# schematics.net
KiCad netlist of a schematic drawn in Altium Designer
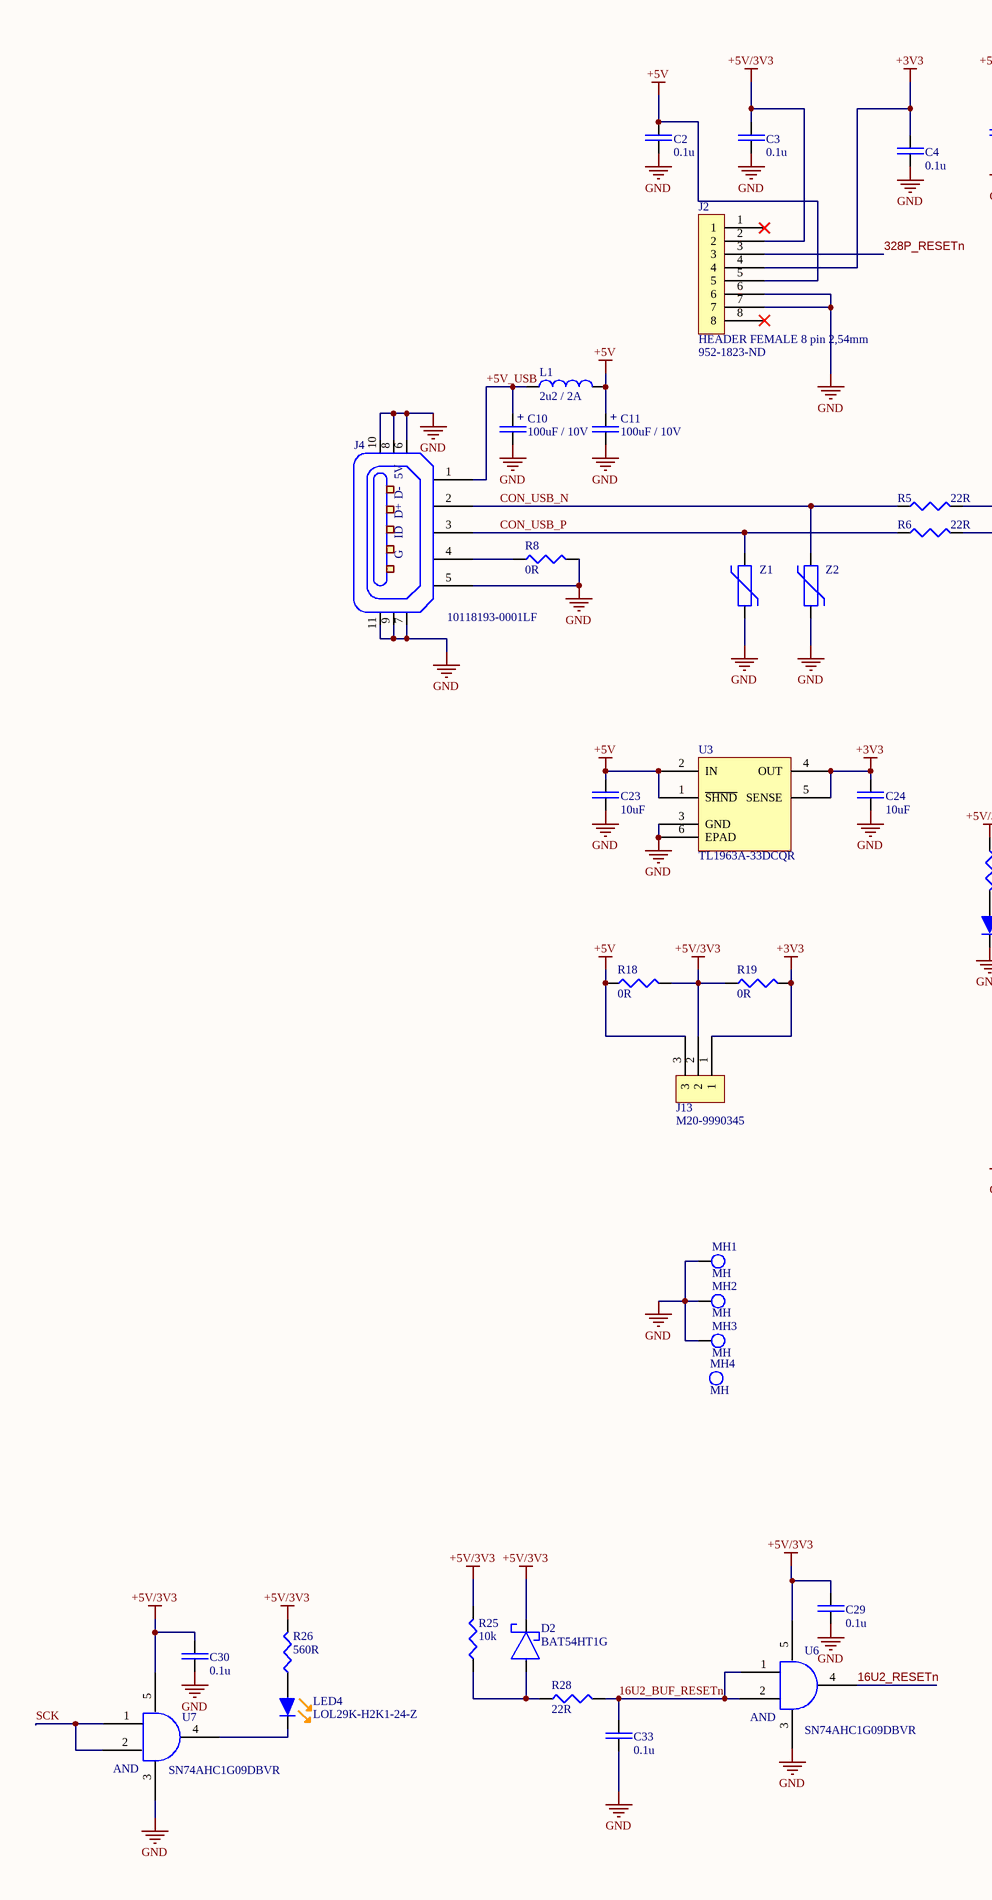
[diagram p0: schematics.SchDoc, left]
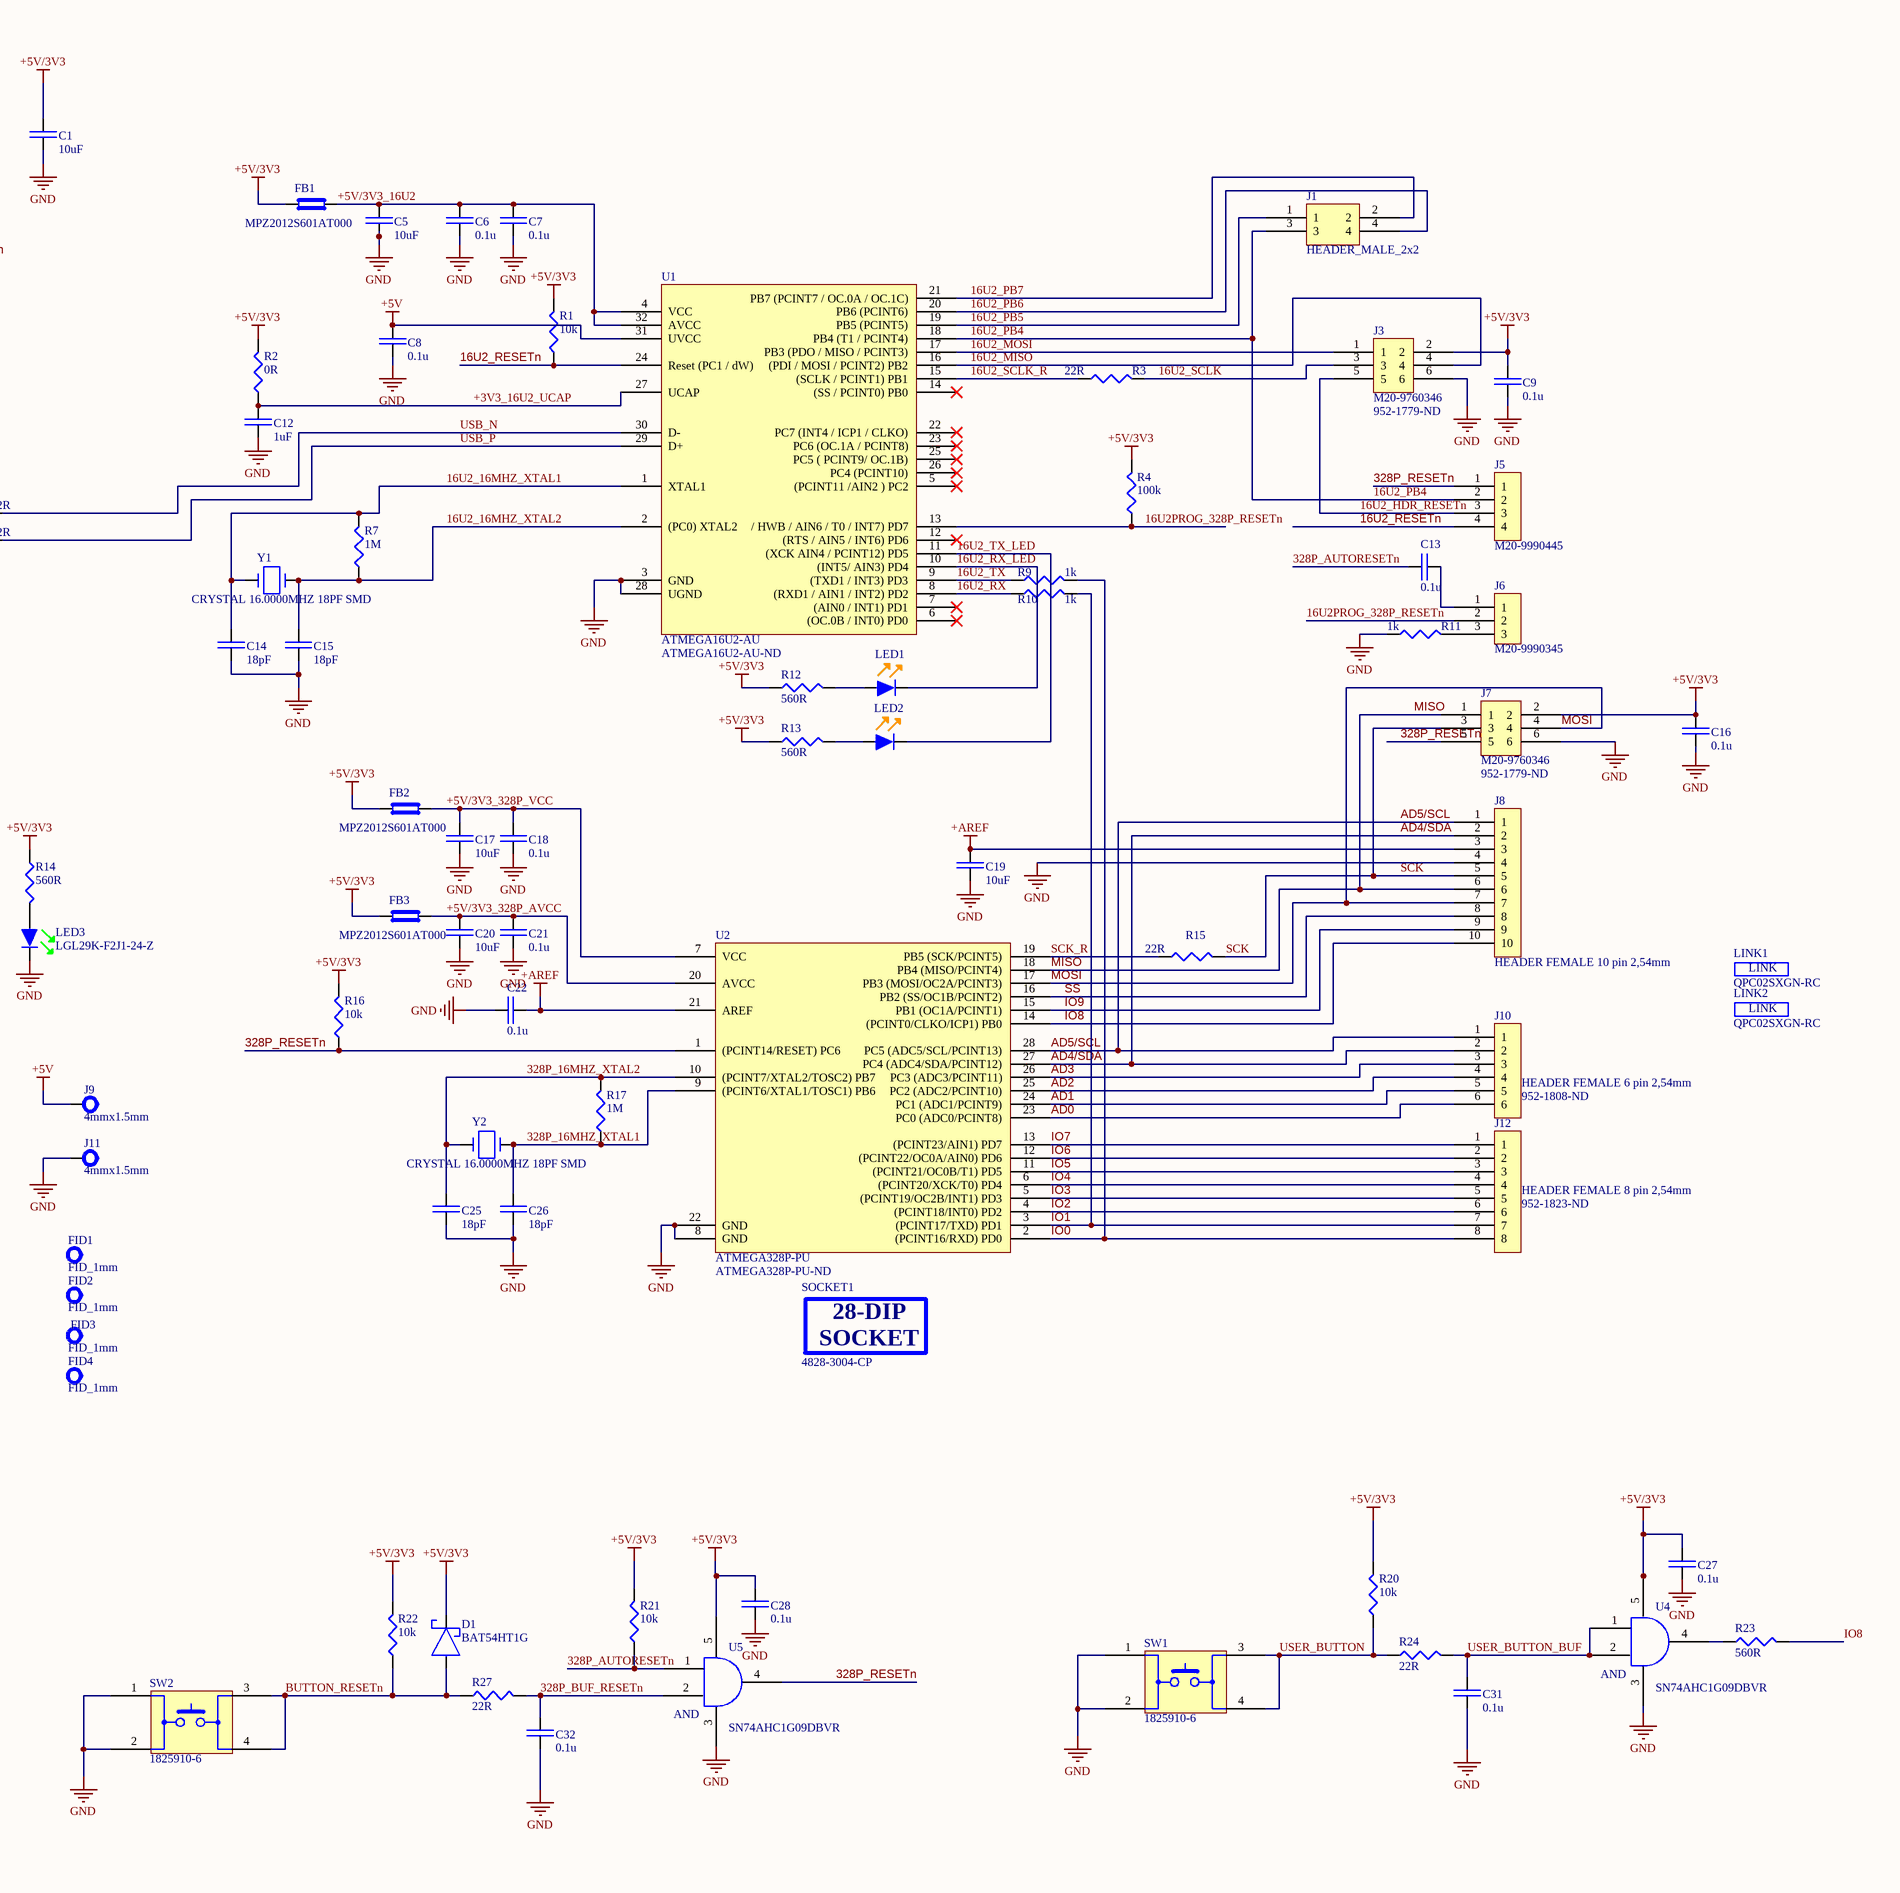
[diagram p1: schematics.SchDoc, right]

(export (version "E")
  (design (tool "Eeschema 10.0.6"))
  (components
    (comp (ref "C1")
      (value "10uF")
      (footprint "CAP_0805")
      (description "Ceramic capacitor SMD 0805 10 µF 16 V 10 %")
      (fields
        (field (name "MANUFACTURER") "Samsung")
        (field (name "MANUFACTURER PART NUMBER") "CL21A106KOQNNNG")
      )
      (libsource (lib "sch_library") (part "CL21A106KOQNNNG"))
    )
    (comp (ref "C2")
      (value "0.1u")
      (footprint "CAP_603")
      (description "CL10 Series 0603 0.1 uF 50 V ±10% Tolerance X7R Multilayer Ceramic Capacitor")
      (fields
        (field (name "MANUFACTURER") "Samsung")
        (field (name "MANUFACTURER PART NUMBER") "CL10B104KB8NNNL")
      )
      (libsource (lib "sch_library") (part "CL10B104KB8NNNL"))
    )
    (comp (ref "C3")
      (value "0.1u")
      (footprint "CAP_603")
      (description "CL10 Series 0603 0.1 uF 50 V ±10% Tolerance X7R Multilayer Ceramic Capacitor")
      (fields
        (field (name "MANUFACTURER") "Samsung")
        (field (name "MANUFACTURER PART NUMBER") "CL10B104KB8NNNL")
      )
      (libsource (lib "sch_library") (part "CL10B104KB8NNNL"))
    )
    (comp (ref "C4")
      (value "0.1u")
      (footprint "CAP_603")
      (description "CL10 Series 0603 0.1 uF 50 V ±10% Tolerance X7R Multilayer Ceramic Capacitor")
      (fields
        (field (name "MANUFACTURER") "Samsung")
        (field (name "MANUFACTURER PART NUMBER") "CL10B104KB8NNNL")
      )
      (libsource (lib "sch_library") (part "CL10B104KB8NNNL"))
    )
    (comp (ref "C5")
      (value "10uF")
      (footprint "CAP_0805")
      (description "Ceramic capacitor SMD 0805 10 µF 16 V 10 %")
      (fields
        (field (name "MANUFACTURER") "Samsung")
        (field (name "MANUFACTURER PART NUMBER") "CL21A106KOQNNNG")
      )
      (libsource (lib "sch_library") (part "CL21A106KOQNNNG"))
    )
    (comp (ref "C6")
      (value "0.1u")
      (footprint "CAP_603")
      (description "CL10 Series 0603 0.1 uF 50 V ±10% Tolerance X7R Multilayer Ceramic Capacitor")
      (fields
        (field (name "MANUFACTURER") "Samsung")
        (field (name "MANUFACTURER PART NUMBER") "CL10B104KB8NNNL")
      )
      (libsource (lib "sch_library") (part "CL10B104KB8NNNL"))
    )
    (comp (ref "C7")
      (value "0.1u")
      (footprint "CAP_603")
      (description "CL10 Series 0603 0.1 uF 50 V ±10% Tolerance X7R Multilayer Ceramic Capacitor")
      (fields
        (field (name "MANUFACTURER") "Samsung")
        (field (name "MANUFACTURER PART NUMBER") "CL10B104KB8NNNL")
      )
      (libsource (lib "sch_library") (part "CL10B104KB8NNNL"))
    )
    (comp (ref "C8")
      (value "0.1u")
      (footprint "CAP_603")
      (description "CL10 Series 0603 0.1 uF 50 V ±10% Tolerance X7R Multilayer Ceramic Capacitor")
      (fields
        (field (name "MANUFACTURER") "Samsung")
        (field (name "MANUFACTURER PART NUMBER") "CL10B104KB8NNNL")
      )
      (libsource (lib "sch_library") (part "CL10B104KB8NNNL"))
    )
    (comp (ref "C9")
      (value "0.1u")
      (footprint "CAP_603")
      (description "CL10 Series 0603 0.1 uF 50 V ±10% Tolerance X7R Multilayer Ceramic Capacitor")
      (fields
        (field (name "MANUFACTURER") "Samsung")
        (field (name "MANUFACTURER PART NUMBER") "CL10B104KB8NNNL")
      )
      (libsource (lib "sch_library") (part "CL10B104KB8NNNL"))
    )
    (comp (ref "C10")
      (value "100uF / 10V")
      (footprint "EEE-1AA101WR")
      (description "Cap Aluminum 100uF 10V 20% (5 X 5.4mm) SMD 50mA 1000 hr 85°C T/R")
      (fields
        (field (name "MANUFACTURER") "Panasonic")
        (field (name "MANUFACTURER PART NUMBER") "EEE-1AA101WR")
      )
      (libsource (lib "sch_library") (part "EEE-1AA101WR"))
    )
    (comp (ref "C11")
      (value "100uF / 10V")
      (footprint "EEE-1AA101WR")
      (description "Cap Aluminum 100uF 10V 20% (5 X 5.4mm) SMD 50mA 1000 hr 85°C T/R")
      (fields
        (field (name "MANUFACTURER") "Panasonic")
        (field (name "MANUFACTURER PART NUMBER") "EEE-1AA101WR")
      )
      (libsource (lib "sch_library") (part "EEE-1AA101WR"))
    )
    (comp (ref "C12")
      (value "1uF")
      (footprint "CAP_603")
      (fields
        (field (name "MANUFACTURER") "Yageo")
        (field (name "MANUFACTURER PART NUMBER") "CC0603KRX5R8BB105")
        (field (name "TOLERANCE") "10%")
      )
      (libsource (lib "sch_library") (part "CC0603KRX5R8BB105"))
    )
    (comp (ref "C13")
      (value "0.1u")
      (footprint "CAP_603")
      (description "CL10 Series 0603 0.1 uF 50 V ±10% Tolerance X7R Multilayer Ceramic Capacitor")
      (fields
        (field (name "MANUFACTURER") "Samsung")
        (field (name "MANUFACTURER PART NUMBER") "CL10B104KB8NNNL")
      )
      (libsource (lib "sch_library") (part "CL10B104KB8NNNL"))
    )
    (comp (ref "C14")
      (value "18pF")
      (footprint "CAP_603")
      (description "0603 18 pF 50V ±5% Tolerance C0G/NP0 Surface Mount Multilayer Ceramic Capacitor")
      (fields
        (field (name "MANUFACTURER") "Kyocera AVX")
        (field (name "MANUFACTURER PART NUMBER") "06035A180JAT2A")
      )
      (libsource (lib "sch_library") (part "06035A180JAT2A"))
    )
    (comp (ref "C15")
      (value "18pF")
      (footprint "CAP_603")
      (description "0603 18 pF 50V ±5% Tolerance C0G/NP0 Surface Mount Multilayer Ceramic Capacitor")
      (fields
        (field (name "MANUFACTURER") "Kyocera AVX")
        (field (name "MANUFACTURER PART NUMBER") "06035A180JAT2A")
      )
      (libsource (lib "sch_library") (part "06035A180JAT2A"))
    )
    (comp (ref "C16")
      (value "0.1u")
      (footprint "CAP_603")
      (description "CL10 Series 0603 0.1 uF 50 V ±10% Tolerance X7R Multilayer Ceramic Capacitor")
      (fields
        (field (name "MANUFACTURER") "Samsung")
        (field (name "MANUFACTURER PART NUMBER") "CL10B104KB8NNNL")
      )
      (libsource (lib "sch_library") (part "CL10B104KB8NNNL"))
    )
    (comp (ref "C17")
      (value "10uF")
      (footprint "CAP_0805")
      (description "Ceramic capacitor SMD 0805 10 µF 16 V 10 %")
      (fields
        (field (name "MANUFACTURER") "Samsung")
        (field (name "MANUFACTURER PART NUMBER") "CL21A106KOQNNNG")
      )
      (libsource (lib "sch_library") (part "CL21A106KOQNNNG"))
    )
    (comp (ref "C18")
      (value "0.1u")
      (footprint "CAP_603")
      (description "CL10 Series 0603 0.1 uF 50 V ±10% Tolerance X7R Multilayer Ceramic Capacitor")
      (fields
        (field (name "MANUFACTURER") "Samsung")
        (field (name "MANUFACTURER PART NUMBER") "CL10B104KB8NNNL")
      )
      (libsource (lib "sch_library") (part "CL10B104KB8NNNL"))
    )
    (comp (ref "C19")
      (value "10uF")
      (footprint "CAP_0805")
      (description "Ceramic capacitor SMD 0805 10 µF 16 V 10 %")
      (fields
        (field (name "MANUFACTURER") "Samsung")
        (field (name "MANUFACTURER PART NUMBER") "CL21A106KOQNNNG")
      )
      (libsource (lib "sch_library") (part "CL21A106KOQNNNG"))
    )
    (comp (ref "C20")
      (value "10uF")
      (footprint "CAP_0805")
      (description "Ceramic capacitor SMD 0805 10 µF 16 V 10 %")
      (fields
        (field (name "MANUFACTURER") "Samsung")
        (field (name "MANUFACTURER PART NUMBER") "CL21A106KOQNNNG")
      )
      (libsource (lib "sch_library") (part "CL21A106KOQNNNG"))
    )
    (comp (ref "C21")
      (value "0.1u")
      (footprint "CAP_603")
      (description "CL10 Series 0603 0.1 uF 50 V ±10% Tolerance X7R Multilayer Ceramic Capacitor")
      (fields
        (field (name "MANUFACTURER") "Samsung")
        (field (name "MANUFACTURER PART NUMBER") "CL10B104KB8NNNL")
      )
      (libsource (lib "sch_library") (part "CL10B104KB8NNNL"))
    )
    (comp (ref "C22")
      (value "0.1u")
      (footprint "CAP_603")
      (description "CL10 Series 0603 0.1 uF 50 V ±10% Tolerance X7R Multilayer Ceramic Capacitor")
      (fields
        (field (name "MANUFACTURER") "Samsung")
        (field (name "MANUFACTURER PART NUMBER") "CL10B104KB8NNNL")
      )
      (libsource (lib "sch_library") (part "CL10B104KB8NNNL"))
    )
    (comp (ref "C23")
      (value "10uF")
      (footprint "CAP_0805")
      (description "Ceramic capacitor SMD 0805 10 µF 16 V 10 %")
      (fields
        (field (name "MANUFACTURER") "Samsung")
        (field (name "MANUFACTURER PART NUMBER") "CL21A106KOQNNNG")
      )
      (libsource (lib "sch_library") (part "CL21A106KOQNNNG"))
    )
    (comp (ref "C24")
      (value "10uF")
      (footprint "CAP_0805")
      (description "Ceramic capacitor SMD 0805 10 µF 16 V 10 %")
      (fields
        (field (name "MANUFACTURER") "Samsung")
        (field (name "MANUFACTURER PART NUMBER") "CL21A106KOQNNNG")
      )
      (libsource (lib "sch_library") (part "CL21A106KOQNNNG"))
    )
    (comp (ref "C25")
      (value "18pF")
      (footprint "CAP_603")
      (description "0603 18 pF 50V ±5% Tolerance C0G/NP0 Surface Mount Multilayer Ceramic Capacitor")
      (fields
        (field (name "MANUFACTURER") "Kyocera AVX")
        (field (name "MANUFACTURER PART NUMBER") "06035A180JAT2A")
      )
      (libsource (lib "sch_library") (part "06035A180JAT2A"))
    )
    (comp (ref "C26")
      (value "18pF")
      (footprint "CAP_603")
      (description "0603 18 pF 50V ±5% Tolerance C0G/NP0 Surface Mount Multilayer Ceramic Capacitor")
      (fields
        (field (name "MANUFACTURER") "Kyocera AVX")
        (field (name "MANUFACTURER PART NUMBER") "06035A180JAT2A")
      )
      (libsource (lib "sch_library") (part "06035A180JAT2A"))
    )
    (comp (ref "C27")
      (value "0.1u")
      (footprint "CAP_603")
      (description "CL10 Series 0603 0.1 uF 50 V ±10% Tolerance X7R Multilayer Ceramic Capacitor")
      (fields
        (field (name "MANUFACTURER") "Samsung")
        (field (name "MANUFACTURER PART NUMBER") "CL10B104KB8NNNL")
      )
      (libsource (lib "sch_library") (part "CL10B104KB8NNNL"))
    )
    (comp (ref "C28")
      (value "0.1u")
      (footprint "CAP_603")
      (description "CL10 Series 0603 0.1 uF 50 V ±10% Tolerance X7R Multilayer Ceramic Capacitor")
      (fields
        (field (name "MANUFACTURER") "Samsung")
        (field (name "MANUFACTURER PART NUMBER") "CL10B104KB8NNNL")
      )
      (libsource (lib "sch_library") (part "CL10B104KB8NNNL"))
    )
    (comp (ref "C29")
      (value "0.1u")
      (footprint "CAP_603")
      (description "CL10 Series 0603 0.1 uF 50 V ±10% Tolerance X7R Multilayer Ceramic Capacitor")
      (fields
        (field (name "MANUFACTURER") "Samsung")
        (field (name "MANUFACTURER PART NUMBER") "CL10B104KB8NNNL")
      )
      (libsource (lib "sch_library") (part "CL10B104KB8NNNL"))
    )
    (comp (ref "C30")
      (value "0.1u")
      (footprint "CAP_603")
      (description "CL10 Series 0603 0.1 uF 50 V ±10% Tolerance X7R Multilayer Ceramic Capacitor")
      (fields
        (field (name "MANUFACTURER") "Samsung")
        (field (name "MANUFACTURER PART NUMBER") "CL10B104KB8NNNL")
      )
      (libsource (lib "sch_library") (part "CL10B104KB8NNNL"))
    )
    (comp (ref "C31")
      (value "0.1u")
      (footprint "CAP_603")
      (description "CL10 Series 0603 0.1 uF 50 V ±10% Tolerance X7R Multilayer Ceramic Capacitor")
      (fields
        (field (name "MANUFACTURER") "Samsung")
        (field (name "MANUFACTURER PART NUMBER") "CL10B104KB8NNNL")
      )
      (libsource (lib "sch_library") (part "CL10B104KB8NNNL"))
    )
    (comp (ref "C32")
      (value "0.1u")
      (footprint "CAP_603")
      (description "CL10 Series 0603 0.1 uF 50 V ±10% Tolerance X7R Multilayer Ceramic Capacitor")
      (fields
        (field (name "MANUFACTURER") "Samsung")
        (field (name "MANUFACTURER PART NUMBER") "CL10B104KB8NNNL")
      )
      (libsource (lib "sch_library") (part "CL10B104KB8NNNL"))
    )
    (comp (ref "C33")
      (value "0.1u")
      (footprint "CAP_603")
      (description "CL10 Series 0603 0.1 uF 50 V ±10% Tolerance X7R Multilayer Ceramic Capacitor")
      (fields
        (field (name "MANUFACTURER") "Samsung")
        (field (name "MANUFACTURER PART NUMBER") "CL10B104KB8NNNL")
      )
      (libsource (lib "sch_library") (part "CL10B104KB8NNNL"))
    )
    (comp (ref "D1")
      (value "BAT54HT1G")
      (footprint "BAT54HT1G")
      (description "Small Signal Schottky Diode, Single, 30 V, 200 mA, 800 mV, 600 mA, 150 C ;RoHS Compliant: Yes")
      (fields (field (name "MANUFACTURER") "ON Semiconductor / Fairchild"))
      (libsource (lib "sch_library") (part "BAT54HT1G"))
    )
    (comp (ref "D2")
      (value "BAT54HT1G")
      (footprint "BAT54HT1G")
      (description "Small Signal Schottky Diode, Single, 30 V, 200 mA, 800 mV, 600 mA, 150 C ;RoHS Compliant: Yes")
      (fields (field (name "MANUFACTURER") "ON Semiconductor / Fairchild"))
      (libsource (lib "sch_library") (part "BAT54HT1G"))
    )
    (comp (ref "FB1")
      (value "MPZ2012S601AT000")
      (footprint "FB_0805")
      (description "FERRITE BEAD 600 OHM 0805 1LN")
      (fields (field (name "MANUFACTURER") "TDK"))
      (libsource (lib "sch_library") (part "MPZ2012S601AT000"))
    )
    (comp (ref "FB2")
      (value "MPZ2012S601AT000")
      (footprint "FB_0805")
      (description "FERRITE BEAD 600 OHM 0805 1LN")
      (fields (field (name "MANUFACTURER") "TDK"))
      (libsource (lib "sch_library") (part "MPZ2012S601AT000"))
    )
    (comp (ref "FB3")
      (value "MPZ2012S601AT000")
      (footprint "FB_0805")
      (description "FERRITE BEAD 600 OHM 0805 1LN")
      (fields (field (name "MANUFACTURER") "TDK"))
      (libsource (lib "sch_library") (part "MPZ2012S601AT000"))
    )
    (comp (ref "FID1")
      (value "FID_1mm")
      (footprint "FID_1mm")
      (description "Fiducial 1mm")
      (libsource (lib "sch_library") (part "FID_1mm"))
    )
    (comp (ref "FID2")
      (value "FID_1mm")
      (footprint "FID_1mm")
      (description "Fiducial 1mm")
      (libsource (lib "sch_library") (part "FID_1mm"))
    )
    (comp (ref "FID3")
      (value "FID_1mm")
      (footprint "FID_1mm")
      (description "Fiducial 1mm")
      (libsource (lib "sch_library") (part "FID_1mm"))
    )
    (comp (ref "FID4")
      (value "FID_1mm")
      (footprint "FID_1mm")
      (description "Fiducial 1mm")
      (libsource (lib "sch_library") (part "FID_1mm"))
    )
    (comp (ref "J1")
      (value "HEADER_MALE_2x2")
      (footprint "HEADER_MALE_2x2PIN")
      (description "02+02 DIL Vert Pin Hdr")
      (fields (field (name "MANUFACTURER") "Harwin") (field (name "MANUFACTURER PART NUMBER") "M20-9760246"))
      (libsource (lib "sch_library") (part "M20-9760246"))
    )
    (comp (ref "J2")
      (value "HEADER FEMALE 8 pin 2,54mm")
      (footprint "HEADER_FEMALE_8PIN_2.54mm")
      (description "2.54mm (0.1\") Pitch SIL Vertical PC Tail Socket Assembly, selective gold + tin, 8 contacts")
      (fields
        (field (name "MANUFACTURER") "Harwin")
        (field (name "MANUFACTURER PART NUMBER") "M20-7820842")
        (field (name "SUPPLIER PART NUMBER 1") "952-1823-ND")
      )
      (libsource (lib "sch_library") (part "M20-7820842"))
    )
    (comp (ref "J3")
      (value "M20-9760346")
      (footprint "HEADER_MALE_2x3PIN")
      (description "03+03 DIL VERT PIN HDR")
      (fields (field (name "MANUFACTURER") "Harwin") (field (name "SUPPLIER PART NUMBER 1") "952-1779-ND"))
      (libsource (lib "sch_library") (part "M20-9760346"))
    )
    (comp (ref "J4")
      (value "10118193-0001LF")
      (footprint "10118193-0001LF")
      (description "CONN USB MICRO B RECPT SMT R/A")
      (fields (field (name "MANUFACTURER") "Amphenol FCI"))
      (libsource (lib "sch_library") (part "10118193-0001LF"))
    )
    (comp (ref "J5")
      (value "M20-9990445")
      (footprint "HEADER_MALE_1x4")
      (fields (field (name "MANUFACTURER") "Harwin"))
      (libsource (lib "sch_library") (part "M20-9990445"))
    )
    (comp (ref "J6")
      (value "M20-9990345")
      (footprint "HEADER_MALE_1x3")
      (fields (field (name "MANUFACTURER") "Harwin"))
      (libsource (lib "sch_library") (part "M20-9990345"))
    )
    (comp (ref "J7")
      (value "M20-9760346")
      (footprint "HEADER_MALE_2x3PIN")
      (description "03+03 DIL VERT PIN HDR")
      (fields (field (name "MANUFACTURER") "Harwin") (field (name "SUPPLIER PART NUMBER 1") "952-1779-ND"))
      (libsource (lib "sch_library") (part "M20-9760346"))
    )
    (comp (ref "J8")
      (value "HEADER FEMALE 10 pin 2,54mm")
      (footprint "HEADER_FEMALE_10PIN_2.54mm")
      (description "Headers & Wire Housings 10 PIN SIL VERTICAL SOCKET GOLD+TIN")
      (fields (field (name "MANUFACTURER") "Harwin") (field (name "MANUFACTURER PART NUMBER") "M20-7821042"))
      (libsource (lib "sch_library") (part "M20-7821042"))
    )
    (comp (ref "J9")
      (value "4mmx1.5mm")
      (footprint "PAD_WITH_HOLE_4mmx1.5mm")
      (libsource (lib "sch_library") (part "PAD_WITH_HOLE_4mmx1.5mm"))
    )
    (comp (ref "J10")
      (value "HEADER FEMALE 6 pin 2,54mm")
      (footprint "HEADER_FEMALE_6PIN_2.54mm")
      (description "Conn Socket Strip SKT 6 POS 2.54mm Solder ST Thru-Hole Tube")
      (fields
        (field (name "MANUFACTURER") "Harwin")
        (field (name "MANUFACTURER PART NUMBER") "M20-7820642")
        (field (name "SUPPLIER PART NUMBER 1") "952-1808-ND")
      )
      (libsource (lib "sch_library") (part "M20-7820642"))
    )
    (comp (ref "J11")
      (value "4mmx1.5mm")
      (footprint "PAD_WITH_HOLE_4mmx1.5mm")
      (libsource (lib "sch_library") (part "PAD_WITH_HOLE_4mmx1.5mm"))
    )
    (comp (ref "J12")
      (value "HEADER FEMALE 8 pin 2,54mm")
      (footprint "HEADER_FEMALE_8PIN_2.54mm")
      (description "2.54mm (0.1\") Pitch SIL Vertical PC Tail Socket Assembly, selective gold + tin, 8 contacts")
      (fields
        (field (name "MANUFACTURER") "Harwin")
        (field (name "MANUFACTURER PART NUMBER") "M20-7820842")
        (field (name "SUPPLIER PART NUMBER 1") "952-1823-ND")
      )
      (libsource (lib "") (part "M20-7820842_1"))
    )
    (comp (ref "J13")
      (value "M20-9990345")
      (footprint "HEADER_MALE_1x3")
      (fields (field (name "MANUFACTURER") "Harwin"))
      (libsource (lib "") (part "M20-9990345_1"))
    )
    (comp (ref "L1")
      (value "2u2 / 2A")
      (footprint "L_1210")
      (description "FIXED IND 2.2UH 2A 80 MOHM SMD")
      (fields
        (field (name "MANUFACTURER") "KEMET")
        (field (name "MANUFACTURER PART NUMBER") "L1210R2R2MDWIT")
      )
      (libsource (lib "sch_library") (part "L1210R2R2MDWIT"))
    )
    (comp (ref "LED1")
      (value "LOL29K-H2K1-24-Z")
      (footprint "LED_0603")
      (description "OSRAM - LO L29K-H2K1-24-Z - SMARTLED 0603 ORANGE")
      (fields (field (name "MANUFACTURER") "Osram Opto"))
      (libsource (lib "sch_library") (part "LOL29K-H2K1-24-Z"))
    )
    (comp (ref "LED2")
      (value "LOL29K-H2K1-24-Z")
      (footprint "LED_0603")
      (description "OSRAM - LO L29K-H2K1-24-Z - SMARTLED 0603 ORANGE")
      (fields (field (name "MANUFACTURER") "Osram Opto"))
      (libsource (lib "sch_library") (part "LOL29K-H2K1-24-Z"))
    )
    (comp (ref "LED3")
      (value "LGL29K-F2J1-24-Z")
      (footprint "LED_0603")
      (description "LED Uni-Color Green 572nm Automotive 2-Pin Chip 0603(1608Metric) T/R")
      (fields (field (name "MANUFACTURER") "Osram Opto"))
      (libsource (lib "sch_library") (part "LGL29K-F2J1-24-Z"))
    )
    (comp (ref "LED4")
      (value "LOL29K-H2K1-24-Z")
      (footprint "LED_0603")
      (description "OSRAM - LO L29K-H2K1-24-Z - SMARTLED 0603 ORANGE")
      (fields (field (name "MANUFACTURER") "Osram Opto"))
      (libsource (lib "sch_library") (part "LOL29K-H2K1-24-Z"))
    )
    (comp (ref "LINK1")
      (value "QPC02SXGN-RC")
      (description "CONN JUMPER SHORTING .100\" GOLD")
      (fields (field (name "MANUFACTURER") "Sullins"))
      (libsource (lib "sch_library") (part "QPC02SXGN-RC"))
    )
    (comp (ref "LINK2")
      (value "QPC02SXGN-RC")
      (description "CONN JUMPER SHORTING .100\" GOLD")
      (fields (field (name "MANUFACTURER") "Sullins"))
      (libsource (lib "sch_library") (part "QPC02SXGN-RC"))
    )
    (comp (ref "MH1")
      (value "MH")
      (footprint "MH_7.4mm_3,2MMD")
      (description "MH_7.4mm_3,2MMD")
      (libsource (lib "sch_library") (part "MH_7.4mm_3,2MMD"))
    )
    (comp (ref "MH2")
      (value "MH")
      (footprint "MH_7.4mm_3,2MMD")
      (description "MH_7.4mm_3,2MMD")
      (libsource (lib "sch_library") (part "MH_7.4mm_3,2MMD"))
    )
    (comp (ref "MH3")
      (value "MH")
      (footprint "MH_7.4mm_3,2MMD")
      (description "MH_7.4mm_3,2MMD")
      (libsource (lib "sch_library") (part "MH_7.4mm_3,2MMD"))
    )
    (comp (ref "MH4")
      (value "MH")
      (footprint "MH_7.4mm_3,2MMD_nonplated")
      (description "MH_7.4mm_3,2MMD non plated")
      (libsource (lib "sch_library") (part "MH_7.4mm_3,2MMD_non_plated"))
    )
    (comp (ref "R1")
      (value "10k")
      (footprint "R_0603")
      (description "RES SMD 10K OHM 1% 1/10W 0603")
      (fields
        (field (name "MANUFACTURER") "Yageo")
        (field (name "MANUFACTURER PART NUMBER") "AC0603FR-0710KL")
      )
      (libsource (lib "sch_library") (part "AC0603FR-0710KL"))
    )
    (comp (ref "R2")
      (value "0R")
      (footprint "R_0603")
      (description "YAGEO - RC0603FR-070RL - RES, THICK FILM, 0R, 1%, 0.1W, 0603")
      (fields
        (field (name "MANUFACTURER") "Yageo")
        (field (name "MANUFACTURER PART NUMBER") "RC0603FR-070RL")
      )
      (libsource (lib "sch_library") (part "RC0603FR-070RL"))
    )
    (comp (ref "R3")
      (value "22R")
      (footprint "R_0805")
      (description "RES SMD 22 OHM 1% 1/8W 0805")
      (fields
        (field (name "MANUFACTURER") "Yageo")
        (field (name "MANUFACTURER PART NUMBER") "RC0805FR-0722RL")
      )
      (libsource (lib "sch_library") (part "RC0805FR-0722RL"))
    )
    (comp (ref "R4")
      (value "100k")
      (footprint "R_0603")
      (description "Res Thick Film 1.6 x 0.8 mm 100K Ohm 1% 0.1W(1/10W) 100ppm/ C Molded SMD Paper T/R")
      (fields
        (field (name "MANUFACTURER") "Yageo")
        (field (name "MANUFACTURER PART NUMBER") "RC0603FR-07100KL")
      )
      (libsource (lib "sch_library") (part "RC0603FR-07100KL"))
    )
    (comp (ref "R5")
      (value "22R")
      (footprint "R_0805")
      (description "RES SMD 22 OHM 1% 1/8W 0805")
      (fields
        (field (name "MANUFACTURER") "Yageo")
        (field (name "MANUFACTURER PART NUMBER") "RC0805FR-0722RL")
      )
      (libsource (lib "sch_library") (part "RC0805FR-0722RL"))
    )
    (comp (ref "R6")
      (value "22R")
      (footprint "R_0805")
      (description "RES SMD 22 OHM 1% 1/8W 0805")
      (fields
        (field (name "MANUFACTURER") "Yageo")
        (field (name "MANUFACTURER PART NUMBER") "RC0805FR-0722RL")
      )
      (libsource (lib "sch_library") (part "RC0805FR-0722RL"))
    )
    (comp (ref "R7")
      (value "1M")
      (footprint "R_0603")
      (description "Yageo RC Series Thick Film Surface Mount Resistor 0603 Case 1M 1% 0.1W 100ppm/C")
      (fields
        (field (name "MANUFACTURER") "Yageo")
        (field (name "MANUFACTURER PART NUMBER") "RC0603FR-071ML")
      )
      (libsource (lib "sch_library") (part "RC0603FR-071ML"))
    )
    (comp (ref "R8")
      (value "0R")
      (footprint "R_0603")
      (description "YAGEO - RC0603FR-070RL - RES, THICK FILM, 0R, 1%, 0.1W, 0603")
      (fields
        (field (name "MANUFACTURER") "Yageo")
        (field (name "MANUFACTURER PART NUMBER") "RC0603FR-070RL")
      )
      (libsource (lib "sch_library") (part "RC0603FR-070RL"))
    )
    (comp (ref "R9")
      (value "1k")
      (footprint "R_0603")
      (description "Res Thick Film 0603 1K Ohm 1% 0.1W(1/10W) ±100ppm/C Epoxy Pad SMD Automotive T/R")
      (fields
        (field (name "MANUFACTURER") "Yageo")
        (field (name "MANUFACTURER PART NUMBER") "AC0603FR-071KL")
      )
      (libsource (lib "sch_library") (part "AC0603FR-071KL"))
    )
    (comp (ref "R10")
      (value "1k")
      (footprint "R_0603")
      (description "Res Thick Film 0603 1K Ohm 1% 0.1W(1/10W) ±100ppm/C Epoxy Pad SMD Automotive T/R")
      (fields
        (field (name "MANUFACTURER") "Yageo")
        (field (name "MANUFACTURER PART NUMBER") "AC0603FR-071KL")
      )
      (libsource (lib "sch_library") (part "AC0603FR-071KL"))
    )
    (comp (ref "R11")
      (value "1k")
      (footprint "R_0603")
      (description "Res Thick Film 0603 1K Ohm 1% 0.1W(1/10W) ±100ppm/C Epoxy Pad SMD Automotive T/R")
      (fields
        (field (name "MANUFACTURER") "Yageo")
        (field (name "MANUFACTURER PART NUMBER") "AC0603FR-071KL")
      )
      (libsource (lib "sch_library") (part "AC0603FR-071KL"))
    )
    (comp (ref "R12")
      (value "560R")
      (footprint "R_0603")
      (fields
        (field (name "MANUFACTURER") "Yageo")
        (field (name "MANUFACTURER PART NUMBER") "RC0603FR-07560RL")
        (field (name "TOLERANCE") "1%")
      )
      (libsource (lib "sch_library") (part "560R"))
    )
    (comp (ref "R13")
      (value "560R")
      (footprint "R_0603")
      (fields
        (field (name "MANUFACTURER") "Yageo")
        (field (name "MANUFACTURER PART NUMBER") "RC0603FR-07560RL")
        (field (name "TOLERANCE") "1%")
      )
      (libsource (lib "sch_library") (part "560R"))
    )
    (comp (ref "R14")
      (value "560R")
      (footprint "R_0603")
      (fields
        (field (name "MANUFACTURER") "Yageo")
        (field (name "MANUFACTURER PART NUMBER") "RC0603FR-07560RL")
        (field (name "TOLERANCE") "1%")
      )
      (libsource (lib "sch_library") (part "560R"))
    )
    (comp (ref "R15")
      (value "22R")
      (footprint "R_0805")
      (description "RES SMD 22 OHM 1% 1/8W 0805")
      (fields
        (field (name "MANUFACTURER") "Yageo")
        (field (name "MANUFACTURER PART NUMBER") "RC0805FR-0722RL")
      )
      (libsource (lib "sch_library") (part "RC0805FR-0722RL"))
    )
    (comp (ref "R16")
      (value "10k")
      (footprint "R_0603")
      (description "RES SMD 10K OHM 1% 1/10W 0603")
      (fields
        (field (name "MANUFACTURER") "Yageo")
        (field (name "MANUFACTURER PART NUMBER") "AC0603FR-0710KL")
      )
      (libsource (lib "sch_library") (part "AC0603FR-0710KL"))
    )
    (comp (ref "R17")
      (value "1M")
      (footprint "R_0603")
      (description "Yageo RC Series Thick Film Surface Mount Resistor 0603 Case 1M 1% 0.1W 100ppm/C")
      (fields
        (field (name "MANUFACTURER") "Yageo")
        (field (name "MANUFACTURER PART NUMBER") "RC0603FR-071ML")
      )
      (libsource (lib "sch_library") (part "RC0603FR-071ML"))
    )
    (comp (ref "R18")
      (value "0R")
      (footprint "R_0603")
      (description "YAGEO - RC0603FR-070RL - RES, THICK FILM, 0R, 1%, 0.1W, 0603")
      (fields
        (field (name "MANUFACTURER") "Yageo")
        (field (name "MANUFACTURER PART NUMBER") "RC0603FR-070RL")
      )
      (libsource (lib "sch_library") (part "RC0603FR-070RL"))
    )
    (comp (ref "R19")
      (value "0R")
      (footprint "R_0603")
      (description "YAGEO - RC0603FR-070RL - RES, THICK FILM, 0R, 1%, 0.1W, 0603")
      (fields
        (field (name "MANUFACTURER") "Yageo")
        (field (name "MANUFACTURER PART NUMBER") "RC0603FR-070RL")
      )
      (libsource (lib "sch_library") (part "RC0603FR-070RL"))
    )
    (comp (ref "R20")
      (value "10k")
      (footprint "R_0603")
      (description "RES SMD 10K OHM 1% 1/10W 0603")
      (fields
        (field (name "MANUFACTURER") "Yageo")
        (field (name "MANUFACTURER PART NUMBER") "AC0603FR-0710KL")
      )
      (libsource (lib "sch_library") (part "AC0603FR-0710KL"))
    )
    (comp (ref "R21")
      (value "10k")
      (footprint "R_0603")
      (description "RES SMD 10K OHM 1% 1/10W 0603")
      (fields
        (field (name "MANUFACTURER") "Yageo")
        (field (name "MANUFACTURER PART NUMBER") "AC0603FR-0710KL")
      )
      (libsource (lib "sch_library") (part "AC0603FR-0710KL"))
    )
    (comp (ref "R22")
      (value "10k")
      (footprint "R_0603")
      (description "RES SMD 10K OHM 1% 1/10W 0603")
      (fields
        (field (name "MANUFACTURER") "Yageo")
        (field (name "MANUFACTURER PART NUMBER") "AC0603FR-0710KL")
      )
      (libsource (lib "sch_library") (part "AC0603FR-0710KL"))
    )
    (comp (ref "R23")
      (value "560R")
      (footprint "R_0603")
      (fields
        (field (name "MANUFACTURER") "Yageo")
        (field (name "MANUFACTURER PART NUMBER") "RC0603FR-07560RL")
        (field (name "TOLERANCE") "1%")
      )
      (libsource (lib "sch_library") (part "560R"))
    )
    (comp (ref "R24")
      (value "22R")
      (footprint "R_0805")
      (description "RES SMD 22 OHM 1% 1/8W 0805")
      (fields
        (field (name "MANUFACTURER") "Yageo")
        (field (name "MANUFACTURER PART NUMBER") "RC0805FR-0722RL")
      )
      (libsource (lib "sch_library") (part "RC0805FR-0722RL"))
    )
    (comp (ref "R25")
      (value "10k")
      (footprint "R_0603")
      (description "RES SMD 10K OHM 1% 1/10W 0603")
      (fields
        (field (name "MANUFACTURER") "Yageo")
        (field (name "MANUFACTURER PART NUMBER") "AC0603FR-0710KL")
      )
      (libsource (lib "sch_library") (part "AC0603FR-0710KL"))
    )
    (comp (ref "R26")
      (value "560R")
      (footprint "R_0603")
      (fields
        (field (name "MANUFACTURER") "Yageo")
        (field (name "MANUFACTURER PART NUMBER") "RC0603FR-07560RL")
        (field (name "TOLERANCE") "1%")
      )
      (libsource (lib "sch_library") (part "560R"))
    )
    (comp (ref "R27")
      (value "22R")
      (footprint "R_0805")
      (description "RES SMD 22 OHM 1% 1/8W 0805")
      (fields
        (field (name "MANUFACTURER") "Yageo")
        (field (name "MANUFACTURER PART NUMBER") "RC0805FR-0722RL")
      )
      (libsource (lib "sch_library") (part "RC0805FR-0722RL"))
    )
    (comp (ref "R28")
      (value "22R")
      (footprint "R_0805")
      (description "RES SMD 22 OHM 1% 1/8W 0805")
      (fields
        (field (name "MANUFACTURER") "Yageo")
        (field (name "MANUFACTURER PART NUMBER") "RC0805FR-0722RL")
      )
      (libsource (lib "sch_library") (part "RC0805FR-0722RL"))
    )
    (comp (ref "SOCKET1")
      (value "4828-3004-CP")
      (description "CONN IC DIP SOCKET 28POS TIN")
      (fields (field (name "MANUFACTURER") "3M"))
      (libsource (lib "sch_library") (part "4828-3004-CP"))
    )
    (comp (ref "SW1")
      (value "1825910-6")
      (footprint "BUTTON")
      (description "SWITCH TACTILE SPST-NO 0.05A 24V")
      (fields (field (name "MANUFACTURER") "TE Connectivity Alcoswitch"))
      (libsource (lib "sch_library") (part "1825910-6"))
    )
    (comp (ref "SW2")
      (value "1825910-6")
      (footprint "BUTTON")
      (description "SWITCH TACTILE SPST-NO 0.05A 24V")
      (fields (field (name "MANUFACTURER") "TE Connectivity Alcoswitch"))
      (libsource (lib "sch_library") (part "1825910-6"))
    )
    (comp (ref "U1")
      (value "ATMEGA16U2-AU")
      (footprint "TQFP32")
      (description "MICROCHIP - ATMEGA16U2-AU - MCU, 8BIT, MEGAAVR, 16MHZ, TQFP-32")
      (fields
        (field (name "MANUFACTURER") "Microchip / Atmel")
        (field (name "SUPPLIER PART NUMBER 1") "ATMEGA16U2-AU-ND")
      )
      (libsource (lib "sch_library") (part "ATMEGA16U2-AU"))
    )
    (comp (ref "U2")
      (value "ATMEGA328P-PU")
      (footprint "DIP28_7.62mm")
      (description "ATMEGA328P-PU; 8 bit Microcontroller AVR 20MHz 1; 32kb Flash; 2kb RAM; I2C SPI 2")
      (fields
        (field (name "MANUFACTURER") "Microchip / Atmel")
        (field (name "SUPPLIER PART NUMBER 1") "ATMEGA328P-PU-ND")
      )
      (libsource (lib "sch_library") (part "ATMEGA328P-PU"))
    )
    (comp (ref "U3")
      (value "TL1963A-33DCQR")
      (footprint "DCQ (R-PDSO-G6)")
      (description "IC REG LINEAR 3.3V 1.5A SOT223-6")
      (fields (field (name "MANUFACTURER") "Texas Instruments"))
      (libsource (lib "sch_library") (part "TL1963A-33DCQR"))
    )
    (comp (ref "U4")
      (value "SN74AHC1G09DBVR")
      (footprint "SOT-23")
      (description "TEXAS INSTRUMENTS - SN74AHC1G09DBVR - AND Gate, 74AHC1G09, 2 Input, 2 V to 5.5 V, SOT-23-5")
      (fields (field (name "MANUFACTURER") "Texas Instruments"))
      (libsource (lib "sch_library") (part "SN74AHC1G09DBVR"))
    )
    (comp (ref "U5")
      (value "SN74AHC1G09DBVR")
      (footprint "SOT-23")
      (description "TEXAS INSTRUMENTS - SN74AHC1G09DBVR - AND Gate, 74AHC1G09, 2 Input, 2 V to 5.5 V, SOT-23-5")
      (fields (field (name "MANUFACTURER") "Texas Instruments"))
      (libsource (lib "sch_library") (part "SN74AHC1G09DBVR"))
    )
    (comp (ref "U6")
      (value "SN74AHC1G09DBVR")
      (footprint "SOT-23")
      (description "TEXAS INSTRUMENTS - SN74AHC1G09DBVR - AND Gate, 74AHC1G09, 2 Input, 2 V to 5.5 V, SOT-23-5")
      (fields (field (name "MANUFACTURER") "Texas Instruments"))
      (libsource (lib "sch_library") (part "SN74AHC1G09DBVR"))
    )
    (comp (ref "U7")
      (value "SN74AHC1G09DBVR")
      (footprint "SOT-23")
      (description "TEXAS INSTRUMENTS - SN74AHC1G09DBVR - AND Gate, 74AHC1G09, 2 Input, 2 V to 5.5 V, SOT-23-5")
      (fields (field (name "MANUFACTURER") "Texas Instruments"))
      (libsource (lib "sch_library") (part "SN74AHC1G09DBVR"))
    )
    (comp (ref "Y1")
      (value "CRYSTAL 16.0000MHZ 18PF SMD")
      (footprint "ABM7_v1_1_BIG")
      (fields
        (field (name "MANUFACTURER") "Abracon")
        (field (name "MANUFACTURER PART NUMBER") "ABM7-16.000MHZ-D2Y-T")
        (field (name "TOLERANCE") "20ppm")
      )
      (libsource (lib "sch_library") (part "ABM7-16.000MHZ-D2Y-T"))
    )
    (comp (ref "Y2")
      (value "CRYSTAL 16.0000MHZ 18PF SMD")
      (footprint "ABM7_v1_1_BIG")
      (fields
        (field (name "MANUFACTURER") "Abracon")
        (field (name "MANUFACTURER PART NUMBER") "ABM7-16.000MHZ-D2Y-T")
        (field (name "TOLERANCE") "20ppm")
      )
      (libsource (lib "sch_library") (part "ABM7-16.000MHZ-D2Y-T"))
    )
    (comp (ref "Z1")
      (value "CG0603MLC-05E")
      (footprint "CG0603MLC-05E")
      (description "VARISTOR 0603")
      (fields (field (name "MANUFACTURER") "Bourns") (field (name "VOLTAGE") "5V"))
      (libsource (lib "sch_library") (part "CG0603MLC-05E"))
    )
    (comp (ref "Z2")
      (value "CG0603MLC-05E")
      (footprint "CG0603MLC-05E")
      (description "VARISTOR 0603")
      (fields (field (name "MANUFACTURER") "Bourns") (field (name "VOLTAGE") "5V"))
      (libsource (lib "sch_library") (part "CG0603MLC-05E"))
    )
  )
  (nets
    (net (code "1") (name "+3V3") (class "Default")
      (node (ref "C24") (pin "2") (pinfunction "2_2") (pintype "passive"))
      (node (ref "C4") (pin "1") (pinfunction "1_1") (pintype "passive"))
      (node (ref "J13") (pin "1") (pinfunction "1_1") (pintype "passive"))
      (node (ref "J2") (pin "4") (pinfunction "4_4") (pintype "passive"))
      (node (ref "R19") (pin "2") (pinfunction "2_2") (pintype "passive"))
      (node (ref "U3") (pin "4") (pinfunction "OUT_4") (pintype "passive"))
      (node (ref "U3") (pin "5") (pinfunction "SENSE_5") (pintype "passive"))
    )
    (net (code "2") (name "+5V") (class "Default")
      (node (ref "C11") (pin "1") (pinfunction "1_1") (pintype "passive"))
      (node (ref "C2") (pin "1") (pinfunction "1_1") (pintype "passive"))
      (node (ref "C23") (pin "2") (pinfunction "2_2") (pintype "passive"))
      (node (ref "C8") (pin "2") (pinfunction "2_2") (pintype "passive"))
      (node (ref "J13") (pin "3") (pinfunction "3_3") (pintype "passive"))
      (node (ref "J2") (pin "5") (pinfunction "5_5") (pintype "passive"))
      (node (ref "J9") (pin "1") (pinfunction "1_1") (pintype "passive"))
      (node (ref "L1") (pin "2") (pinfunction "2_2") (pintype "passive"))
      (node (ref "R18") (pin "1") (pinfunction "1_1") (pintype "passive"))
      (node (ref "U1") (pin "31") (pinfunction "UVCC_31") (pintype "passive"))
      (node (ref "U3") (pin "1") (pinfunction "~{SHND}_1") (pintype "passive"))
      (node (ref "U3") (pin "2") (pinfunction "IN_2") (pintype "passive"))
    )
    (net (code "3") (name "+5V{slash}3V3") (class "Default")
      (node (ref "C1") (pin "2") (pinfunction "2_2") (pintype "passive"))
      (node (ref "C16") (pin "2") (pinfunction "2_2") (pintype "passive"))
      (node (ref "C27") (pin "1") (pinfunction "1_1") (pintype "passive"))
      (node (ref "C28") (pin "1") (pinfunction "1_1") (pintype "passive"))
      (node (ref "C29") (pin "1") (pinfunction "1_1") (pintype "passive"))
      (node (ref "C3") (pin "1") (pinfunction "1_1") (pintype "passive"))
      (node (ref "C30") (pin "2") (pinfunction "2_2") (pintype "passive"))
      (node (ref "C9") (pin "2") (pinfunction "2_2") (pintype "passive"))
      (node (ref "D1") (pin "1") (pinfunction "1_1") (pintype "passive"))
      (node (ref "D2") (pin "1") (pinfunction "1_1") (pintype "passive"))
      (node (ref "FB1") (pin "1") (pinfunction "1_1") (pintype "passive"))
      (node (ref "FB2") (pin "1") (pinfunction "1_1") (pintype "passive"))
      (node (ref "FB3") (pin "1") (pinfunction "1_1") (pintype "passive"))
      (node (ref "J13") (pin "2") (pinfunction "2_2") (pintype "passive"))
      (node (ref "J2") (pin "2") (pinfunction "2_2") (pintype "passive"))
      (node (ref "J3") (pin "2") (pinfunction "2_2") (pintype "passive"))
      (node (ref "J7") (pin "2") (pinfunction "2_2") (pintype "passive"))
      (node (ref "R1") (pin "2") (pinfunction "2_2") (pintype "passive"))
      (node (ref "R12") (pin "1") (pinfunction "1_1") (pintype "passive"))
      (node (ref "R13") (pin "1") (pinfunction "1_1") (pintype "passive"))
      (node (ref "R14") (pin "1") (pinfunction "1_1") (pintype "passive"))
      (node (ref "R16") (pin "2") (pinfunction "2_2") (pintype "passive"))
      (node (ref "R18") (pin "2") (pinfunction "2_2") (pintype "passive"))
      (node (ref "R19") (pin "1") (pinfunction "1_1") (pintype "passive"))
      (node (ref "R2") (pin "2") (pinfunction "2_2") (pintype "passive"))
      (node (ref "R20") (pin "2") (pinfunction "2_2") (pintype "passive"))
      (node (ref "R21") (pin "2") (pinfunction "2_2") (pintype "passive"))
      (node (ref "R22") (pin "2") (pinfunction "2_2") (pintype "passive"))
      (node (ref "R25") (pin "2") (pinfunction "2_2") (pintype "passive"))
      (node (ref "R26") (pin "2") (pinfunction "2_2") (pintype "passive"))
      (node (ref "R4") (pin "2") (pinfunction "2_2") (pintype "passive"))
      (node (ref "U4") (pin "5") (pinfunction "5_5") (pintype "passive"))
      (node (ref "U5") (pin "5") (pinfunction "5_5") (pintype "passive"))
      (node (ref "U6") (pin "5") (pinfunction "5_5") (pintype "passive"))
      (node (ref "U7") (pin "5") (pinfunction "5_5") (pintype "passive"))
    )
    (net (code "4") (name "+AREF") (class "Default")
      (node (ref "C19") (pin "2") (pinfunction "2_2") (pintype "passive"))
      (node (ref "C22") (pin "2") (pinfunction "2_2") (pintype "passive"))
      (node (ref "J8") (pin "3") (pinfunction "3_3") (pintype "passive"))
      (node (ref "U2") (pin "21") (pinfunction "AREF_21") (pintype "passive"))
    )
    (net (code "5") (name "/+3V3_16U2_UCAP") (class "Default")
      (node (ref "C12") (pin "2") (pinfunction "2_2") (pintype "passive"))
      (node (ref "R2") (pin "1") (pinfunction "1_1") (pintype "passive"))
      (node (ref "U1") (pin "27") (pinfunction "UCAP_27") (pintype "passive"))
    )
    (net (code "6") (name "/+5V_USB") (class "Default")
      (node (ref "C10") (pin "1") (pinfunction "1_1") (pintype "passive"))
      (node (ref "J4") (pin "1") (pinfunction "1_1") (pintype "passive"))
      (node (ref "L1") (pin "1") (pinfunction "1_1") (pintype "passive"))
    )
    (net (code "7") (name "/+5V{slash}3V3_16U2") (class "Default")
      (node (ref "C5") (pin "2") (pinfunction "2_2") (pintype "passive"))
      (node (ref "C6") (pin "2") (pinfunction "2_2") (pintype "passive"))
      (node (ref "C7") (pin "2") (pinfunction "2_2") (pintype "passive"))
      (node (ref "FB1") (pin "2") (pinfunction "2_2") (pintype "passive"))
      (node (ref "U1") (pin "32") (pinfunction "AVCC_32") (pintype "passive"))
      (node (ref "U1") (pin "4") (pinfunction "VCC_4") (pintype "passive"))
    )
    (net (code "8") (name "/+5V{slash}3V3_328P_AVCC") (class "Default")
      (node (ref "C20") (pin "2") (pinfunction "2_2") (pintype "passive"))
      (node (ref "C21") (pin "2") (pinfunction "2_2") (pintype "passive"))
      (node (ref "FB3") (pin "2") (pinfunction "2_2") (pintype "passive"))
      (node (ref "U2") (pin "20") (pinfunction "AVCC_20") (pintype "passive"))
    )
    (net (code "9") (name "/+5V{slash}3V3_328P_VCC") (class "Default")
      (node (ref "C17") (pin "2") (pinfunction "2_2") (pintype "passive"))
      (node (ref "C18") (pin "2") (pinfunction "2_2") (pintype "passive"))
      (node (ref "FB2") (pin "2") (pinfunction "2_2") (pintype "passive"))
      (node (ref "U2") (pin "7") (pinfunction "VCC_7") (pintype "passive"))
    )
    (net (code "10") (name "/16U2PROG_328P_RESETn") (class "Default")
      (node (ref "J6") (pin "2") (pinfunction "2_2") (pintype "passive"))
      (node (ref "R4") (pin "1") (pinfunction "1_1") (pintype "passive"))
      (node (ref "U1") (pin "13") (pinfunction "/_HWB_/_AIN6_/_T0_/_INT7)_PD7_13") (pintype "passive"))
    )
    (net (code "11") (name "/16U2_16MHZ_XTAL1") (class "Default")
      (node (ref "C14") (pin "2") (pinfunction "2_2") (pintype "passive"))
      (node (ref "R7") (pin "2") (pinfunction "2_2") (pintype "passive"))
      (node (ref "U1") (pin "1") (pinfunction "XTAL1_1") (pintype "passive"))
      (node (ref "Y1") (pin "1") (pinfunction "1_1") (pintype "passive"))
    )
    (net (code "12") (name "/16U2_16MHZ_XTAL2") (class "Default")
      (node (ref "C15") (pin "2") (pinfunction "2_2") (pintype "passive"))
      (node (ref "R7") (pin "1") (pinfunction "1_1") (pintype "passive"))
      (node (ref "U1") (pin "2") (pinfunction "(PC0)_XTAL2_2") (pintype "passive"))
      (node (ref "Y1") (pin "2") (pinfunction "2_2") (pintype "passive"))
    )
    (net (code "13") (name "/16U2_BUF_RESETn") (class "Default")
      (node (ref "C33") (pin "2") (pinfunction "2_2") (pintype "passive"))
      (node (ref "R28") (pin "2") (pinfunction "2_2") (pintype "passive"))
      (node (ref "U6") (pin "1") (pinfunction "1_1") (pintype "passive"))
      (node (ref "U6") (pin "2") (pinfunction "2_2") (pintype "passive"))
    )
    (net (code "14") (name "/16U2_HDR_RESETn") (class "Default")
      (node (ref "J3") (pin "5") (pinfunction "5_5") (pintype "passive"))
      (node (ref "J5") (pin "3") (pinfunction "3_3") (pintype "passive"))
    )
    (net (code "15") (name "/16U2_MISO") (class "Default")
      (node (ref "J3") (pin "4") (pinfunction "4_4") (pintype "passive"))
      (node (ref "U1") (pin "16") (pinfunction "(PDI_/_MOSI_/_PCINT2)_PB2_16") (pintype "passive"))
    )
    (net (code "16") (name "/16U2_MOSI") (class "Default")
      (node (ref "J3") (pin "1") (pinfunction "1_1") (pintype "passive"))
      (node (ref "U1") (pin "17") (pinfunction "PB3_(PDO_/_MISO_/_PCINT3)_17") (pintype "passive"))
    )
    (net (code "17") (name "/16U2_PB4") (class "Default")
      (node (ref "J1") (pin "3") (pinfunction "3_3") (pintype "passive"))
      (node (ref "J5") (pin "2") (pinfunction "2_2") (pintype "passive"))
      (node (ref "U1") (pin "18") (pinfunction "PB4_(T1_/_PCINT4)_18") (pintype "passive"))
    )
    (net (code "18") (name "/16U2_PB5") (class "Default")
      (node (ref "J1") (pin "1") (pinfunction "1_1") (pintype "passive"))
      (node (ref "U1") (pin "19") (pinfunction "PB5_(PCINT5)_19") (pintype "passive"))
    )
    (net (code "19") (name "/16U2_PB6") (class "Default")
      (node (ref "J1") (pin "4") (pinfunction "4_4") (pintype "passive"))
      (node (ref "U1") (pin "20") (pinfunction "PB6_(PCINT6)_20") (pintype "passive"))
    )
    (net (code "20") (name "/16U2_PB7") (class "Default")
      (node (ref "J1") (pin "2") (pinfunction "2_2") (pintype "passive"))
      (node (ref "U1") (pin "21") (pinfunction "PB7_(PCINT7_/_OC.0A_/_OC.1C)_21") (pintype "passive"))
    )
    (net (code "21") (name "/16U2_RESETn") (class "Default")
      (node (ref "J5") (pin "4") (pinfunction "4_4") (pintype "passive"))
      (node (ref "R1") (pin "1") (pinfunction "1_1") (pintype "passive"))
      (node (ref "U1") (pin "24") (pinfunction "Reset_(PC1_/_dW)_24") (pintype "passive"))
      (node (ref "U6") (pin "4") (pinfunction "4_4") (pintype "passive"))
    )
    (net (code "22") (name "/16U2_RX") (class "Default")
      (node (ref "R10") (pin "1") (pinfunction "1_1") (pintype "passive"))
      (node (ref "U1") (pin "8") (pinfunction "(RXD1_/_AIN1_/_INT2)_PD2_8") (pintype "passive"))
    )
    (net (code "23") (name "/16U2_RX_LED") (class "Default")
      (node (ref "LED1") (pin "1") (pinfunction "1_1") (pintype "passive"))
      (node (ref "U1") (pin "10") (pinfunction "(INT5/_AIN3)_PD4_10") (pintype "passive"))
    )
    (net (code "24") (name "/16U2_SCLK") (class "Default")
      (node (ref "J3") (pin "3") (pinfunction "3_3") (pintype "passive"))
      (node (ref "R3") (pin "2") (pinfunction "2_2") (pintype "passive"))
    )
    (net (code "25") (name "/16U2_SCLK_R") (class "Default")
      (node (ref "R3") (pin "1") (pinfunction "1_1") (pintype "passive"))
      (node (ref "U1") (pin "15") (pinfunction "(SCLK_/_PCINT1)_PB1_15") (pintype "passive"))
    )
    (net (code "26") (name "/16U2_TX") (class "Default")
      (node (ref "R9") (pin "1") (pinfunction "1_1") (pintype "passive"))
      (node (ref "U1") (pin "9") (pinfunction "(TXD1_/_INT3)_PD3_9") (pintype "passive"))
    )
    (net (code "27") (name "/16U2_TX_LED") (class "Default")
      (node (ref "LED2") (pin "1") (pinfunction "1_1") (pintype "passive"))
      (node (ref "U1") (pin "11") (pinfunction "(XCK_AIN4_/_PCINT12)_PD5_11") (pintype "passive"))
    )
    (net (code "28") (name "/328P_16MHZ_XTAL1") (class "Default")
      (node (ref "C26") (pin "2") (pinfunction "2_2") (pintype "passive"))
      (node (ref "R17") (pin "1") (pinfunction "1_1") (pintype "passive"))
      (node (ref "U2") (pin "9") (pinfunction "(PCINT6/XTAL1/TOSC1)_PB6_9") (pintype "passive"))
      (node (ref "Y2") (pin "2") (pinfunction "2_2") (pintype "passive"))
    )
    (net (code "29") (name "/328P_16MHZ_XTAL2") (class "Default")
      (node (ref "C25") (pin "2") (pinfunction "2_2") (pintype "passive"))
      (node (ref "R17") (pin "2") (pinfunction "2_2") (pintype "passive"))
      (node (ref "U2") (pin "10") (pinfunction "(PCINT7/XTAL2/TOSC2)_PB7_10") (pintype "passive"))
      (node (ref "Y2") (pin "1") (pinfunction "1_1") (pintype "passive"))
    )
    (net (code "30") (name "/328P_AUTORESETn") (class "Default")
      (node (ref "C13") (pin "1") (pinfunction "1_1") (pintype "passive"))
      (node (ref "R21") (pin "1") (pinfunction "1_1") (pintype "passive"))
      (node (ref "U5") (pin "1") (pinfunction "1_1") (pintype "passive"))
    )
    (net (code "31") (name "/328P_BUF_RESETn") (class "Default")
      (node (ref "C32") (pin "2") (pinfunction "2_2") (pintype "passive"))
      (node (ref "R27") (pin "2") (pinfunction "2_2") (pintype "passive"))
      (node (ref "U5") (pin "2") (pinfunction "2_2") (pintype "passive"))
    )
    (net (code "32") (name "/328P_RESETn") (class "Default")
      (node (ref "J2") (pin "3") (pinfunction "3_3") (pintype "passive"))
      (node (ref "J5") (pin "1") (pinfunction "1_1") (pintype "passive"))
      (node (ref "J7") (pin "5") (pinfunction "5_5") (pintype "passive"))
      (node (ref "R16") (pin "1") (pinfunction "1_1") (pintype "passive"))
      (node (ref "U2") (pin "1") (pinfunction "(PCINT14/RESET)_PC6_1") (pintype "passive"))
      (node (ref "U5") (pin "4") (pinfunction "4_4") (pintype "passive"))
    )
    (net (code "33") (name "/AD0") (class "Default")
      (node (ref "J10") (pin "6") (pinfunction "6_6") (pintype "passive"))
      (node (ref "U2") (pin "23") (pinfunction "PC0_(ADC0/PCINT8)_23") (pintype "passive"))
    )
    (net (code "34") (name "/AD1") (class "Default")
      (node (ref "J10") (pin "5") (pinfunction "5_5") (pintype "passive"))
      (node (ref "U2") (pin "24") (pinfunction "PC1_(ADC1/PCINT9)_24") (pintype "passive"))
    )
    (net (code "35") (name "/AD2") (class "Default")
      (node (ref "J10") (pin "4") (pinfunction "4_4") (pintype "passive"))
      (node (ref "U2") (pin "25") (pinfunction "PC2_(ADC2/PCINT10)_25") (pintype "passive"))
    )
    (net (code "36") (name "/AD3") (class "Default")
      (node (ref "J10") (pin "3") (pinfunction "3_3") (pintype "passive"))
      (node (ref "U2") (pin "26") (pinfunction "PC3_(ADC3/PCINT11)_26") (pintype "passive"))
    )
    (net (code "37") (name "/AD4{slash}SDA") (class "Default")
      (node (ref "J10") (pin "2") (pinfunction "2_2") (pintype "passive"))
      (node (ref "J8") (pin "2") (pinfunction "2_2") (pintype "passive"))
      (node (ref "U2") (pin "27") (pinfunction "PC4_(ADC4/SDA/PCINT12)_27") (pintype "passive"))
    )
    (net (code "38") (name "/AD5{slash}SCL") (class "Default")
      (node (ref "J10") (pin "1") (pinfunction "1_1") (pintype "passive"))
      (node (ref "J8") (pin "1") (pinfunction "1_1") (pintype "passive"))
      (node (ref "U2") (pin "28") (pinfunction "PC5_(ADC5/SCL/PCINT13)_28") (pintype "passive"))
    )
    (net (code "39") (name "/BUTTON_RESETn") (class "Default")
      (node (ref "D1") (pin "2") (pinfunction "2_2") (pintype "passive"))
      (node (ref "R22") (pin "1") (pinfunction "1_1") (pintype "passive"))
      (node (ref "R27") (pin "1") (pinfunction "1_1") (pintype "passive"))
      (node (ref "SW2") (pin "3") (pinfunction "3_3") (pintype "passive"))
      (node (ref "SW2") (pin "4") (pinfunction "4_4") (pintype "passive"))
    )
    (net (code "40") (name "/CON_USB_N") (class "Default")
      (node (ref "J4") (pin "2") (pinfunction "2_2") (pintype "passive"))
      (node (ref "R5") (pin "1") (pinfunction "1_1") (pintype "passive"))
      (node (ref "Z2") (pin "2") (pinfunction "2_2") (pintype "passive"))
    )
    (net (code "41") (name "/CON_USB_P") (class "Default")
      (node (ref "J4") (pin "3") (pinfunction "3_3") (pintype "passive"))
      (node (ref "R6") (pin "1") (pinfunction "1_1") (pintype "passive"))
      (node (ref "Z1") (pin "2") (pinfunction "2_2") (pintype "passive"))
    )
    (net (code "42") (name "/IO0") (class "Default")
      (node (ref "J12") (pin "8") (pinfunction "8_8") (pintype "passive"))
      (node (ref "R9") (pin "2") (pinfunction "2_2") (pintype "passive"))
      (node (ref "U2") (pin "2") (pinfunction "(PCINT16/RXD)_PD0_2") (pintype "passive"))
    )
    (net (code "43") (name "/IO1") (class "Default")
      (node (ref "J12") (pin "7") (pinfunction "7_7") (pintype "passive"))
      (node (ref "R10") (pin "2") (pinfunction "2_2") (pintype "passive"))
      (node (ref "U2") (pin "3") (pinfunction "(PCINT17/TXD)_PD1_3") (pintype "passive"))
    )
    (net (code "44") (name "/IO2") (class "Default")
      (node (ref "J12") (pin "6") (pinfunction "6_6") (pintype "passive"))
      (node (ref "U2") (pin "4") (pinfunction "(PCINT18/INT0)_PD2_4") (pintype "passive"))
    )
    (net (code "45") (name "/IO3") (class "Default")
      (node (ref "J12") (pin "5") (pinfunction "5_5") (pintype "passive"))
      (node (ref "U2") (pin "5") (pinfunction "(PCINT19/OC2B/INT1)_PD3_5") (pintype "passive"))
    )
    (net (code "46") (name "/IO4") (class "Default")
      (node (ref "J12") (pin "4") (pinfunction "4_4") (pintype "passive"))
      (node (ref "U2") (pin "6") (pinfunction "(PCINT20/XCK/T0)_PD4_6") (pintype "passive"))
    )
    (net (code "47") (name "/IO5") (class "Default")
      (node (ref "J12") (pin "3") (pinfunction "3_3") (pintype "passive"))
      (node (ref "U2") (pin "11") (pinfunction "(PCINT21/OC0B/T1)_PD5_11") (pintype "passive"))
    )
    (net (code "48") (name "/IO6") (class "Default")
      (node (ref "J12") (pin "2") (pinfunction "2_2") (pintype "passive"))
      (node (ref "U2") (pin "12") (pinfunction "(PCINT22/OC0A/AIN0)_PD6_12") (pintype "passive"))
    )
    (net (code "49") (name "/IO7") (class "Default")
      (node (ref "J12") (pin "1") (pinfunction "1_1") (pintype "passive"))
      (node (ref "U2") (pin "13") (pinfunction "(PCINT23/AIN1)_PD7_13") (pintype "passive"))
    )
    (net (code "50") (name "/IO8") (class "Default")
      (node (ref "J8") (pin "10") (pinfunction "10_10") (pintype "passive"))
      (node (ref "R23") (pin "2") (pinfunction "2_2") (pintype "passive"))
      (node (ref "U2") (pin "14") (pinfunction "(PCINT0/CLKO/ICP1)_PB0_14") (pintype "passive"))
    )
    (net (code "51") (name "/IO9") (class "Default")
      (node (ref "J8") (pin "9") (pinfunction "9_9") (pintype "passive"))
      (node (ref "U2") (pin "15") (pinfunction "PB1_(OC1A/PCINT1)_15") (pintype "passive"))
    )
    (net (code "52") (name "/MISO") (class "Default")
      (node (ref "J7") (pin "1") (pinfunction "1_1") (pintype "passive"))
      (node (ref "J8") (pin "6") (pinfunction "6_6") (pintype "passive"))
      (node (ref "U2") (pin "18") (pinfunction "PB4_(MISO/PCINT4)_18") (pintype "passive"))
    )
    (net (code "53") (name "/MOSI") (class "Default")
      (node (ref "J7") (pin "4") (pinfunction "4_4") (pintype "passive"))
      (node (ref "J8") (pin "7") (pinfunction "7_7") (pintype "passive"))
      (node (ref "U2") (pin "17") (pinfunction "PB3_(MOSI/OC2A/PCINT3)_17") (pintype "passive"))
    )
    (net (code "54") (name "/SCK") (class "Default")
      (node (ref "J7") (pin "3") (pinfunction "3_3") (pintype "passive"))
      (node (ref "J8") (pin "5") (pinfunction "5_5") (pintype "passive"))
      (node (ref "R15") (pin "2") (pinfunction "2_2") (pintype "passive"))
      (node (ref "U7") (pin "1") (pinfunction "1_1") (pintype "passive"))
      (node (ref "U7") (pin "2") (pinfunction "2_2") (pintype "passive"))
    )
    (net (code "55") (name "/SCK_R") (class "Default")
      (node (ref "R15") (pin "1") (pinfunction "1_1") (pintype "passive"))
      (node (ref "U2") (pin "19") (pinfunction "PB5_(SCK/PCINT5)_19") (pintype "passive"))
    )
    (net (code "56") (name "/SS") (class "Default")
      (node (ref "J8") (pin "8") (pinfunction "8_8") (pintype "passive"))
      (node (ref "U2") (pin "16") (pinfunction "PB2_(SS/OC1B/PCINT2)_16") (pintype "passive"))
    )
    (net (code "57") (name "/USB_N") (class "Default")
      (node (ref "R5") (pin "2") (pinfunction "2_2") (pintype "passive"))
      (node (ref "U1") (pin "30") (pinfunction "D-_30") (pintype "passive"))
    )
    (net (code "58") (name "/USB_P") (class "Default")
      (node (ref "R6") (pin "2") (pinfunction "2_2") (pintype "passive"))
      (node (ref "U1") (pin "29") (pinfunction "D+_29") (pintype "passive"))
    )
    (net (code "59") (name "/USER_BUTTON") (class "Default")
      (node (ref "R20") (pin "1") (pinfunction "1_1") (pintype "passive"))
      (node (ref "R24") (pin "1") (pinfunction "1_1") (pintype "passive"))
      (node (ref "SW1") (pin "3") (pinfunction "3_3") (pintype "passive"))
      (node (ref "SW1") (pin "4") (pinfunction "4_4") (pintype "passive"))
    )
    (net (code "60") (name "/USER_BUTTON_BUF") (class "Default")
      (node (ref "C31") (pin "2") (pinfunction "2_2") (pintype "passive"))
      (node (ref "R24") (pin "2") (pinfunction "2_2") (pintype "passive"))
      (node (ref "U4") (pin "1") (pinfunction "1_1") (pintype "passive"))
      (node (ref "U4") (pin "2") (pinfunction "2_2") (pintype "passive"))
    )
    (net (code "61") (name "GND") (class "Default")
      (node (ref "C1") (pin "1") (pinfunction "1_1") (pintype "passive"))
      (node (ref "C10") (pin "2") (pinfunction "2_2") (pintype "passive"))
      (node (ref "C11") (pin "2") (pinfunction "2_2") (pintype "passive"))
      (node (ref "C12") (pin "1") (pinfunction "1_1") (pintype "passive"))
      (node (ref "C14") (pin "1") (pinfunction "1_1") (pintype "passive"))
      (node (ref "C15") (pin "1") (pinfunction "1_1") (pintype "passive"))
      (node (ref "C16") (pin "1") (pinfunction "1_1") (pintype "passive"))
      (node (ref "C17") (pin "1") (pinfunction "1_1") (pintype "passive"))
      (node (ref "C18") (pin "1") (pinfunction "1_1") (pintype "passive"))
      (node (ref "C19") (pin "1") (pinfunction "1_1") (pintype "passive"))
      (node (ref "C2") (pin "2") (pinfunction "2_2") (pintype "passive"))
      (node (ref "C20") (pin "1") (pinfunction "1_1") (pintype "passive"))
      (node (ref "C21") (pin "1") (pinfunction "1_1") (pintype "passive"))
      (node (ref "C22") (pin "1") (pinfunction "1_1") (pintype "passive"))
      (node (ref "C23") (pin "1") (pinfunction "1_1") (pintype "passive"))
      (node (ref "C24") (pin "1") (pinfunction "1_1") (pintype "passive"))
      (node (ref "C25") (pin "1") (pinfunction "1_1") (pintype "passive"))
      (node (ref "C26") (pin "1") (pinfunction "1_1") (pintype "passive"))
      (node (ref "C27") (pin "2") (pinfunction "2_2") (pintype "passive"))
      (node (ref "C28") (pin "2") (pinfunction "2_2") (pintype "passive"))
      (node (ref "C29") (pin "2") (pinfunction "2_2") (pintype "passive"))
      (node (ref "C3") (pin "2") (pinfunction "2_2") (pintype "passive"))
      (node (ref "C30") (pin "1") (pinfunction "1_1") (pintype "passive"))
      (node (ref "C31") (pin "1") (pinfunction "1_1") (pintype "passive"))
      (node (ref "C32") (pin "1") (pinfunction "1_1") (pintype "passive"))
      (node (ref "C33") (pin "1") (pinfunction "1_1") (pintype "passive"))
      (node (ref "C4") (pin "2") (pinfunction "2_2") (pintype "passive"))
      (node (ref "C5") (pin "1") (pinfunction "1_1") (pintype "passive"))
      (node (ref "C6") (pin "1") (pinfunction "1_1") (pintype "passive"))
      (node (ref "C7") (pin "1") (pinfunction "1_1") (pintype "passive"))
      (node (ref "C8") (pin "1") (pinfunction "1_1") (pintype "passive"))
      (node (ref "C9") (pin "1") (pinfunction "1_1") (pintype "passive"))
      (node (ref "J11") (pin "1") (pinfunction "1_1") (pintype "passive"))
      (node (ref "J2") (pin "6") (pinfunction "6_6") (pintype "passive"))
      (node (ref "J2") (pin "7") (pinfunction "7_7") (pintype "passive"))
      (node (ref "J3") (pin "6") (pinfunction "6_6") (pintype "passive"))
      (node (ref "J4") (pin "10") (pinfunction "10_10") (pintype "passive"))
      (node (ref "J4") (pin "11") (pinfunction "11_11") (pintype "passive"))
      (node (ref "J4") (pin "5") (pinfunction "5_5") (pintype "passive"))
      (node (ref "J4") (pin "6") (pinfunction "6_6") (pintype "passive"))
      (node (ref "J4") (pin "7") (pinfunction "7_7") (pintype "passive"))
      (node (ref "J4") (pin "8") (pinfunction "8_8") (pintype "passive"))
      (node (ref "J4") (pin "9") (pinfunction "9_9") (pintype "passive"))
      (node (ref "J7") (pin "6") (pinfunction "6_6") (pintype "passive"))
      (node (ref "J8") (pin "4") (pinfunction "4_4") (pintype "passive"))
      (node (ref "LED3") (pin "1") (pinfunction "1_1") (pintype "passive"))
      (node (ref "MH1") (pin "1") (pinfunction "1_1") (pintype "passive"))
      (node (ref "MH2") (pin "1") (pinfunction "1_1") (pintype "passive"))
      (node (ref "MH3") (pin "1") (pinfunction "1_1") (pintype "passive"))
      (node (ref "R11") (pin "1") (pinfunction "1_1") (pintype "passive"))
      (node (ref "R8") (pin "2") (pinfunction "2_2") (pintype "passive"))
      (node (ref "SW1") (pin "1") (pinfunction "1_1") (pintype "passive"))
      (node (ref "SW1") (pin "2") (pinfunction "2_2") (pintype "passive"))
      (node (ref "SW2") (pin "1") (pinfunction "1_1") (pintype "passive"))
      (node (ref "SW2") (pin "2") (pinfunction "2_2") (pintype "passive"))
      (node (ref "U1") (pin "28") (pinfunction "UGND_28") (pintype "passive"))
      (node (ref "U1") (pin "3") (pinfunction "GND_3") (pintype "passive"))
      (node (ref "U2") (pin "22") (pinfunction "GND_22") (pintype "passive"))
      (node (ref "U2") (pin "8") (pinfunction "GND_8") (pintype "passive"))
      (node (ref "U3") (pin "3") (pinfunction "GND_3") (pintype "passive"))
      (node (ref "U3") (pin "6") (pinfunction "EPAD_6") (pintype "passive"))
      (node (ref "U4") (pin "3") (pinfunction "3_3") (pintype "passive"))
      (node (ref "U5") (pin "3") (pinfunction "3_3") (pintype "passive"))
      (node (ref "U6") (pin "3") (pinfunction "3_3") (pintype "passive"))
      (node (ref "U7") (pin "3") (pinfunction "3_3") (pintype "passive"))
      (node (ref "Z1") (pin "1") (pinfunction "1_1") (pintype "passive"))
      (node (ref "Z2") (pin "1") (pinfunction "1_1") (pintype "passive"))
    )
    (net (code "62") (name "Net-(C13-Pad2)") (class "Default")
      (node (ref "C13") (pin "2") (pinfunction "2_2") (pintype "passive"))
      (node (ref "J6") (pin "1") (pinfunction "1_1") (pintype "passive"))
    )
    (net (code "63") (name "Net-(D2-Pad2)") (class "Default")
      (node (ref "D2") (pin "2") (pinfunction "2_2") (pintype "passive"))
      (node (ref "R25") (pin "1") (pinfunction "1_1") (pintype "passive"))
      (node (ref "R28") (pin "1") (pinfunction "1_1") (pintype "passive"))
    )
    (net (code "64") (name "Net-(J4-Pad4)") (class "Default")
      (node (ref "J4") (pin "4") (pinfunction "4_4") (pintype "passive"))
      (node (ref "R8") (pin "1") (pinfunction "1_1") (pintype "passive"))
    )
    (net (code "65") (name "Net-(J6-Pad3)") (class "Default")
      (node (ref "J6") (pin "3") (pinfunction "3_3") (pintype "passive"))
      (node (ref "R11") (pin "2") (pinfunction "2_2") (pintype "passive"))
    )
    (net (code "66") (name "Net-(LED1-Pad2)") (class "Default")
      (node (ref "LED1") (pin "2") (pinfunction "2_2") (pintype "passive"))
      (node (ref "R12") (pin "2") (pinfunction "2_2") (pintype "passive"))
    )
    (net (code "67") (name "Net-(LED2-Pad2)") (class "Default")
      (node (ref "LED2") (pin "2") (pinfunction "2_2") (pintype "passive"))
      (node (ref "R13") (pin "2") (pinfunction "2_2") (pintype "passive"))
    )
    (net (code "68") (name "Net-(LED3-Pad2)") (class "Default")
      (node (ref "LED3") (pin "2") (pinfunction "2_2") (pintype "passive"))
      (node (ref "R14") (pin "2") (pinfunction "2_2") (pintype "passive"))
    )
    (net (code "69") (name "Net-(LED4-Pad1)") (class "Default")
      (node (ref "LED4") (pin "1") (pinfunction "1_1") (pintype "passive"))
      (node (ref "U7") (pin "4") (pinfunction "4_4") (pintype "passive"))
    )
    (net (code "70") (name "Net-(LED4-Pad2)") (class "Default")
      (node (ref "LED4") (pin "2") (pinfunction "2_2") (pintype "passive"))
      (node (ref "R26") (pin "1") (pinfunction "1_1") (pintype "passive"))
    )
    (net (code "71") (name "Net-(R23-Pad1)") (class "Default")
      (node (ref "R23") (pin "1") (pinfunction "1_1") (pintype "passive"))
      (node (ref "U4") (pin "4") (pinfunction "4_4") (pintype "passive"))
    )
    (net (code "72") (name "unconnected-(J2-Pad1)") (class "Default")
      (node (ref "J2") (pin "1") (pinfunction "1_1") (pintype "passive+no_connect"))
    )
    (net (code "73") (name "unconnected-(J2-Pad8)") (class "Default")
      (node (ref "J2") (pin "8") (pinfunction "8_8") (pintype "passive+no_connect"))
    )
    (net (code "74") (name "unconnected-(U1-(AIN0_{slash}_INT1)_PD1-Pad7)") (class "Default")
      (node (ref "U1") (pin "7") (pinfunction "(AIN0_/_INT1)_PD1_7") (pintype "passive+no_connect"))
    )
    (net (code "75") (name "unconnected-(U1-(OC.0B_{slash}_INT0)_PD0-Pad6)") (class "Default")
      (node (ref "U1") (pin "6") (pinfunction "(OC.0B_/_INT0)_PD0_6") (pintype "passive+no_connect"))
    )
    (net (code "76") (name "unconnected-(U1-(PCINT11_{slash}AIN2_)_PC2-Pad5)") (class "Default")
      (node (ref "U1") (pin "5") (pinfunction "(PCINT11_/AIN2_)_PC2_5") (pintype "passive+no_connect"))
    )
    (net (code "77") (name "unconnected-(U1-(RTS_{slash}_AIN5_{slash}_INT6)_PD6-Pad12)") (class "Default")
      (node (ref "U1") (pin "12") (pinfunction "(RTS_/_AIN5_/_INT6)_PD6_12") (pintype "passive+no_connect"))
    )
    (net (code "78") (name "unconnected-(U1-(SS_{slash}_PCINT0)_PB0-Pad14)") (class "Default")
      (node (ref "U1") (pin "14") (pinfunction "(SS_/_PCINT0)_PB0_14") (pintype "passive+no_connect"))
    )
    (net (code "79") (name "unconnected-(U1-PC4_(PCINT10)-Pad26)") (class "Default")
      (node (ref "U1") (pin "26") (pinfunction "PC4_(PCINT10)_26") (pintype "passive+no_connect"))
    )
    (net (code "80") (name "unconnected-(U1-PC5_(_PCINT9{slash}_OC.1B)-Pad25)") (class "Default")
      (node (ref "U1") (pin "25") (pinfunction "PC5_(_PCINT9/_OC.1B)_25") (pintype "passive+no_connect"))
    )
    (net (code "81") (name "unconnected-(U1-PC6_(OC.1A_{slash}_PCINT8)-Pad23)") (class "Default")
      (node (ref "U1") (pin "23") (pinfunction "PC6_(OC.1A_/_PCINT8)_23") (pintype "passive+no_connect"))
    )
    (net (code "82") (name "unconnected-(U1-PC7_(INT4_{slash}_ICP1_{slash}_CLKO)-Pad22)") (class "Default")
      (node (ref "U1") (pin "22") (pinfunction "PC7_(INT4_/_ICP1_/_CLKO)_22") (pintype "passive+no_connect"))
    )
  )
)
